# TaaraESP-THBL.net
KiCad netlist of a schematic drawn in EAGLE
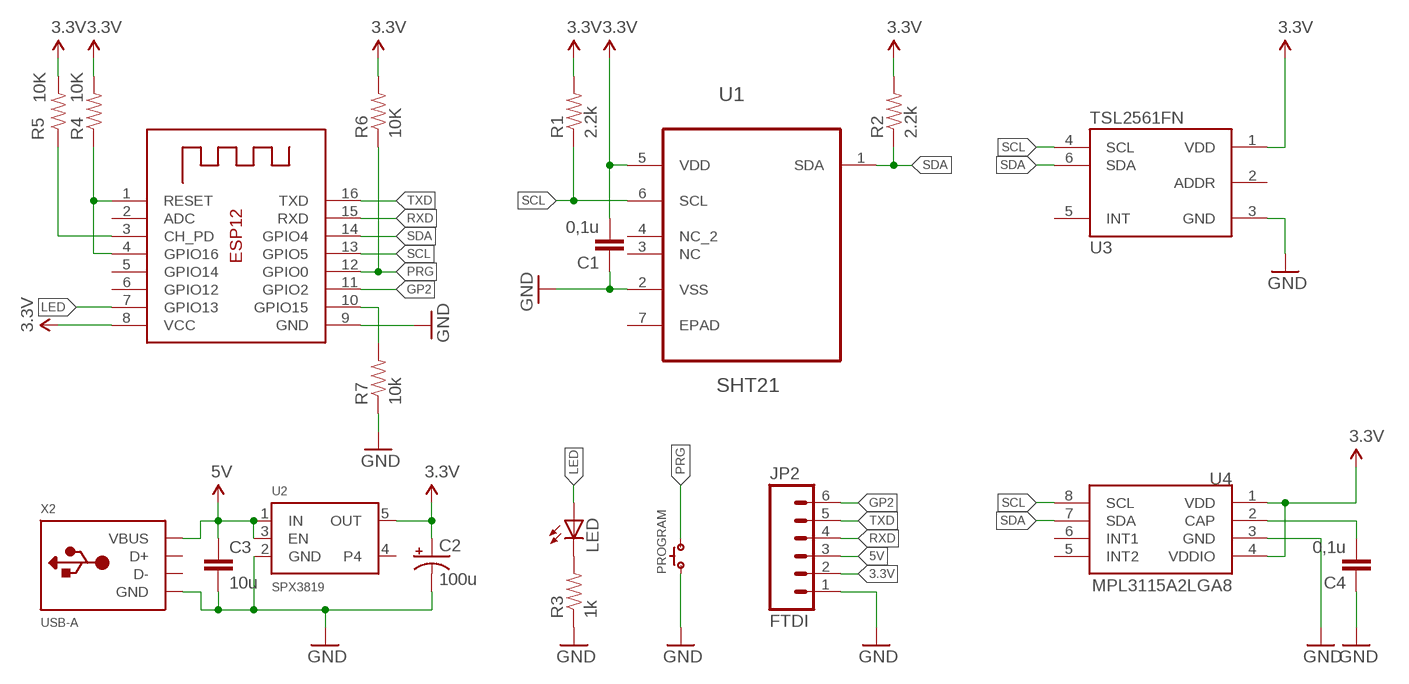
[diagram p0: schematic, sheet 1]

(export (version "E")
  (design (tool "Eeschema 10.0.6"))
  (components
    (comp (ref "C1")
      (value "0,1u")
      (footprint "eagle-import:0603-CAP")
      (libsource (lib "eagle-import") (part "CAP0603-CAP"))
    )
    (comp (ref "C2")
      (value "100u")
      (footprint "eagle-import:EIA3216")
      (libsource (lib "eagle-import") (part "CAP_POL1206"))
    )
    (comp (ref "C3")
      (value "10u")
      (footprint "eagle-import:0603-CAP")
      (libsource (lib "eagle-import") (part "CAP0603-CAP"))
    )
    (comp (ref "C4")
      (value "0,1u")
      (footprint "eagle-import:0603-CAP")
      (libsource (lib "eagle-import") (part "CAP0603-CAP"))
    )
    (comp (ref "JP2")
      (value "FTDI")
      (footprint "eagle-import:1X06-SIP_LOCK")
      (libsource (lib "eagle-import") (part "M06SIP_LOCK"))
    )
    (comp (ref "LED")
      (value "LEDCHIPLED_0603")
      (footprint "eagle-import:CHIPLED_0603")
      (libsource (lib "eagle-import") (part "LEDCHIPLED_0603"))
    )
    (comp (ref "PROGRAM")
      (value "SPST.B3U-1000P(M)-B")
      (footprint "eagle-import:B3U-1000P(M)-B")
      (libsource (lib "eagle-import") (part "SPST.B3U-1000P(M)-B"))
    )
    (comp (ref "R1")
      (value "2.2k")
      (footprint "eagle-import:0603-RES")
      (libsource (lib "eagle-import") (part "RESISTOR0603-RES"))
    )
    (comp (ref "R2")
      (value "2.2k")
      (footprint "eagle-import:0603-RES")
      (libsource (lib "eagle-import") (part "RESISTOR0603-RES"))
    )
    (comp (ref "R3")
      (value "1k")
      (footprint "eagle-import:0603-RES")
      (libsource (lib "eagle-import") (part "RESISTOR0603-RES"))
    )
    (comp (ref "R4")
      (value "10K")
      (footprint "eagle-import:0603-RES")
      (libsource (lib "eagle-import") (part "RESISTOR0603-RES"))
    )
    (comp (ref "R5")
      (value "10K")
      (footprint "eagle-import:0603-RES")
      (libsource (lib "eagle-import") (part "RESISTOR0603-RES"))
    )
    (comp (ref "R6")
      (value "10K")
      (footprint "eagle-import:0603-RES")
      (libsource (lib "eagle-import") (part "RESISTOR0603-RES"))
    )
    (comp (ref "R7")
      (value "10k")
      (footprint "eagle-import:0603-RES")
      (libsource (lib "eagle-import") (part "RESISTOR0603-RES"))
    )
    (comp (ref "U1")
      (value "SHT21")
      (footprint "eagle-import:DFN300X300X110-7N")
      (libsource (lib "eagle-import") (part "SHT21"))
    )
    (comp (ref "U2")
      (value "SPX3819")
      (footprint "eagle-import:SOT23-5")
      (libsource (lib "eagle-import") (part "VREG_SOT23-5"))
    )
    (comp (ref "U3")
      (value "TSL2561FN")
      (footprint "eagle-import:FN-6")
      (libsource (lib "eagle-import") (part "TSL2561FN"))
    )
    (comp (ref "U4")
      (value "MPL3115A2LGA8")
      (footprint "eagle-import:LGA8")
      (libsource (lib "eagle-import") (part "MPL3115A2LGA8"))
    )
    (comp (ref "X1")
      (value "ESP-12")
      (footprint "eagle-import:ESP-12")
      (libsource (lib "eagle-import") (part "ESP-12"))
    )
    (comp (ref "X2")
      (value "USB-A")
      (footprint "eagle-import:MOLEX_480371000")
      (libsource (lib "eagle-import") (part "USB-A"))
    )
  )
  (nets
    (net (code "1") (name "3.3V") (class "Default")
      (node (ref "C1") (pin "2") (pinfunction "2_2") (pintype "passive"))
      (node (ref "C2") (pin "A") (pinfunction "+_A") (pintype "passive"))
      (node (ref "JP2") (pin "2") (pinfunction "2_2") (pintype "passive"))
      (node (ref "R1") (pin "2") (pinfunction "2_2") (pintype "passive"))
      (node (ref "R2") (pin "2") (pinfunction "2_2") (pintype "passive"))
      (node (ref "R4") (pin "2") (pinfunction "2_2") (pintype "passive"))
      (node (ref "R5") (pin "2") (pinfunction "2_2") (pintype "passive"))
      (node (ref "R6") (pin "2") (pinfunction "2_2") (pintype "passive"))
      (node (ref "U1") (pin "5") (pinfunction "VDD_5") (pintype "power_in"))
      (node (ref "U2") (pin "5") (pinfunction "OUT_5") (pintype "power_in"))
      (node (ref "U3") (pin "1") (pinfunction "VDD_1") (pintype "power_in"))
      (node (ref "U4") (pin "1") (pinfunction "VDD_1") (pintype "bidirectional"))
      (node (ref "U4") (pin "4") (pinfunction "VDDIO_4") (pintype "bidirectional"))
      (node (ref "X1") (pin "8") (pinfunction "VCC_8") (pintype "power_in"))
    )
    (net (code "2") (name "5V") (class "Default")
      (node (ref "C3") (pin "1") (pinfunction "1_1") (pintype "passive"))
      (node (ref "JP2") (pin "3") (pinfunction "3_3") (pintype "passive"))
      (node (ref "U2") (pin "1") (pinfunction "IN_1") (pintype "power_in"))
      (node (ref "U2") (pin "3") (pinfunction "EN_3") (pintype "input"))
      (node (ref "X2") (pin "1") (pinfunction "VBUS_1") (pintype "power_in"))
    )
    (net (code "3") (name "GND") (class "Default")
      (node (ref "C1") (pin "1") (pinfunction "1_1") (pintype "passive"))
      (node (ref "C2") (pin "C") (pinfunction "-_C") (pintype "passive"))
      (node (ref "C3") (pin "2") (pinfunction "2_2") (pintype "passive"))
      (node (ref "C4") (pin "1") (pinfunction "1_1") (pintype "passive"))
      (node (ref "JP2") (pin "1") (pinfunction "1_1") (pintype "passive"))
      (node (ref "PROGRAM") (pin "1") (pinfunction "1_1") (pintype "bidirectional"))
      (node (ref "R3") (pin "1") (pinfunction "1_1") (pintype "passive"))
      (node (ref "R7") (pin "1") (pinfunction "1_1") (pintype "passive"))
      (node (ref "U1") (pin "2") (pinfunction "VSS_2") (pintype "power_in"))
      (node (ref "U2") (pin "2") (pinfunction "GND_2") (pintype "power_in"))
      (node (ref "U3") (pin "3") (pinfunction "GND_3") (pintype "power_in"))
      (node (ref "U4") (pin "3") (pinfunction "GND_3") (pintype "bidirectional"))
      (node (ref "X1") (pin "9") (pinfunction "GND_9") (pintype "power_in"))
      (node (ref "X2") (pin "4") (pinfunction "GND_4") (pintype "power_in"))
    )
    (net (code "4") (name "GP2") (class "Default")
      (node (ref "JP2") (pin "6") (pinfunction "6_6") (pintype "passive"))
      (node (ref "X1") (pin "11") (pinfunction "GPIO2_11") (pintype "bidirectional"))
    )
    (net (code "5") (name "LED") (class "Default")
      (node (ref "LED") (pin "A") (pinfunction "A_A") (pintype "passive"))
      (node (ref "X1") (pin "7") (pinfunction "GPIO13_7") (pintype "bidirectional"))
    )
    (net (code "6") (name "Net-(LED-PadC)") (class "Default")
      (node (ref "LED") (pin "C") (pinfunction "C_C") (pintype "passive"))
      (node (ref "R3") (pin "2") (pinfunction "2_2") (pintype "passive"))
    )
    (net (code "7") (name "Net-(U4-CAP)") (class "Default")
      (node (ref "C4") (pin "2") (pinfunction "2_2") (pintype "passive"))
      (node (ref "U4") (pin "2") (pinfunction "CAP_2") (pintype "bidirectional"))
    )
    (net (code "8") (name "Net-(X1-CH_PD)") (class "Default")
      (node (ref "R5") (pin "1") (pinfunction "1_1") (pintype "passive"))
      (node (ref "X1") (pin "3") (pinfunction "CH_PD_3") (pintype "input"))
    )
    (net (code "9") (name "Net-(X1-GPIO15)") (class "Default")
      (node (ref "R7") (pin "2") (pinfunction "2_2") (pintype "passive"))
      (node (ref "X1") (pin "10") (pinfunction "GPIO15_10") (pintype "bidirectional"))
    )
    (net (code "10") (name "Net-(X1-GPIO16)") (class "Default")
      (node (ref "R4") (pin "1") (pinfunction "1_1") (pintype "passive"))
      (node (ref "X1") (pin "1") (pinfunction "RESET_1") (pintype "input"))
      (node (ref "X1") (pin "4") (pinfunction "GPIO16_4") (pintype "bidirectional"))
    )
    (net (code "11") (name "PRG") (class "Default")
      (node (ref "PROGRAM") (pin "2") (pinfunction "2_2") (pintype "bidirectional"))
      (node (ref "R6") (pin "1") (pinfunction "1_1") (pintype "passive"))
      (node (ref "X1") (pin "12") (pinfunction "GPIO0_12") (pintype "bidirectional"))
    )
    (net (code "12") (name "RXD") (class "Default")
      (node (ref "JP2") (pin "4") (pinfunction "4_4") (pintype "passive"))
      (node (ref "X1") (pin "15") (pinfunction "RXD_15") (pintype "input"))
    )
    (net (code "13") (name "SCL") (class "Default")
      (node (ref "R1") (pin "1") (pinfunction "1_1") (pintype "passive"))
      (node (ref "U1") (pin "6") (pinfunction "SCL_6") (pintype "input"))
      (node (ref "U3") (pin "4") (pinfunction "SCL_4") (pintype "input"))
      (node (ref "U4") (pin "8") (pinfunction "SCL_8") (pintype "bidirectional"))
      (node (ref "X1") (pin "13") (pinfunction "GPIO5_13") (pintype "bidirectional"))
    )
    (net (code "14") (name "SDA") (class "Default")
      (node (ref "R2") (pin "1") (pinfunction "1_1") (pintype "passive"))
      (node (ref "U1") (pin "1") (pinfunction "SDA_1") (pintype "bidirectional"))
      (node (ref "U3") (pin "6") (pinfunction "SDA_6") (pintype "bidirectional"))
      (node (ref "U4") (pin "7") (pinfunction "SDA_7") (pintype "bidirectional"))
      (node (ref "X1") (pin "14") (pinfunction "GPIO4_14") (pintype "bidirectional"))
    )
    (net (code "15") (name "TXD") (class "Default")
      (node (ref "JP2") (pin "5") (pinfunction "5_5") (pintype "passive"))
      (node (ref "X1") (pin "16") (pinfunction "TXD_16") (pintype "output"))
    )
    (net (code "16") (name "unconnected-(U1-EPAD-Pad7)") (class "Default")
      (node (ref "U1") (pin "7") (pinfunction "EPAD_7") (pintype "passive"))
    )
    (net (code "17") (name "unconnected-(U1-NC-Pad3)") (class "Default")
      (node (ref "U1") (pin "3") (pinfunction "NC_3") (pintype "no_connect"))
    )
    (net (code "18") (name "unconnected-(U1-NC_2-Pad4)") (class "Default")
      (node (ref "U1") (pin "4") (pinfunction "NC_2_4") (pintype "no_connect"))
    )
    (net (code "19") (name "unconnected-(U2-P4-Pad4)") (class "Default")
      (node (ref "U2") (pin "4") (pinfunction "P4_4") (pintype "bidirectional"))
    )
    (net (code "20") (name "unconnected-(U3-ADDR-Pad2)") (class "Default")
      (node (ref "U3") (pin "2") (pinfunction "ADDR_2") (pintype "input"))
    )
    (net (code "21") (name "unconnected-(U3-INT-Pad5)") (class "Default")
      (node (ref "U3") (pin "5") (pinfunction "INT_5") (pintype "output"))
    )
    (net (code "22") (name "unconnected-(U4-INT1-Pad6)") (class "Default")
      (node (ref "U4") (pin "6") (pinfunction "INT1_6") (pintype "bidirectional"))
    )
    (net (code "23") (name "unconnected-(U4-INT2-Pad5)") (class "Default")
      (node (ref "U4") (pin "5") (pinfunction "INT2_5") (pintype "bidirectional"))
    )
    (net (code "24") (name "unconnected-(X1-ADC-Pad2)") (class "Default")
      (node (ref "X1") (pin "2") (pinfunction "ADC_2") (pintype "passive"))
    )
    (net (code "25") (name "unconnected-(X1-GPIO12-Pad6)") (class "Default")
      (node (ref "X1") (pin "6") (pinfunction "GPIO12_6") (pintype "bidirectional"))
    )
    (net (code "26") (name "unconnected-(X1-GPIO14-Pad5)") (class "Default")
      (node (ref "X1") (pin "5") (pinfunction "GPIO14_5") (pintype "bidirectional"))
    )
    (net (code "27") (name "unconnected-(X2-D+-Pad3)") (class "Default")
      (node (ref "X2") (pin "3") (pinfunction "D+_3") (pintype "bidirectional"))
    )
    (net (code "28") (name "unconnected-(X2-D--Pad2)") (class "Default")
      (node (ref "X2") (pin "2") (pinfunction "D-_2") (pintype "bidirectional"))
    )
  )
)
